# imu.net
KiCad netlist of a schematic drawn in Altium Designer
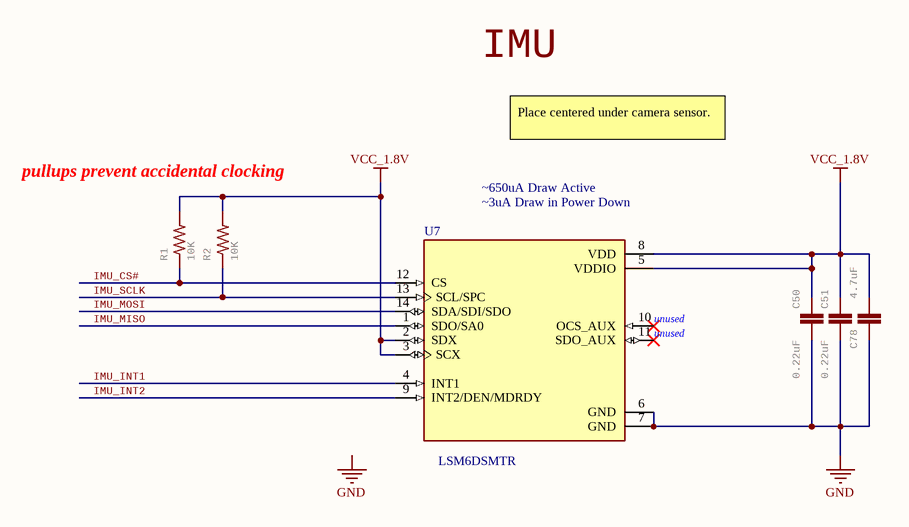
[diagram p0: imu.SchDoc]

(export (version "E")
  (design (tool "Eeschema 10.0.6"))
  (components
    (comp (ref "C50")
      (value "0.22uF")
      (footprint "C0201")
      (description "CAPACITOR, European symbol")
      (fields (field (name "MPN") "GRM033R60J224ME15D"))
      (libsource (lib "openmv-ae3") (part "C-EUC0201"))
    )
    (comp (ref "C51")
      (value "0.22uF")
      (footprint "C0201")
      (description "CAPACITOR, European symbol")
      (fields (field (name "MPN") "GRM033R60J224ME15D"))
      (libsource (lib "openmv-ae3") (part "C-EUC0201"))
    )
    (comp (ref "C78")
      (value "4.7uF")
      (footprint "0402-CAP")
      (description "0402 (1005 Metric) Nick Garner - TeleSense")
      (fields (field (name "MPN") "JMK105BBJ475MV-F"))
      (libsource (lib "openmv-ae3") (part "CAP_0402"))
    )
    (comp (ref "R1")
      (value "10K")
      (footprint "R0201")
      (fields (field (name "LIBRARYNAME") "sfe"))
      (libsource (lib "openmv-ae3") (part "RESISTOR0402-RES"))
    )
    (comp (ref "R2")
      (value "10K")
      (footprint "R0201")
      (fields (field (name "LIBRARYNAME") "sfe"))
      (libsource (lib "openmv-ae3") (part "RESISTOR0402-RES"))
    )
    (comp (ref "U7")
      (value "~")
      (footprint "LSM6DSMTR")
      (description "Accelerometer, Gyroscope, Temperature, 6 Axis Sensor IÂ²C, SPI Output")
      (fields
        (field (name "MF") "STMicroelectronics")
        (field (name "MP") "LSM6DSMTR")
        (field (name "MPN") "LSM6DSMTR")
      )
      (libsource (lib "openmv-ae3") (part "LSM6DSMTR"))
    )
  )
  (nets
    (net (code "1") (name "/IMU_CS#") (class "Default")
      (node (ref "R1") (pin "1") (pinfunction "1_1") (pintype "passive"))
      (node (ref "U7") (pin "12") (pinfunction "CS_12") (pintype "input"))
    )
    (net (code "2") (name "/IMU_INT1") (class "Default")
      (node (ref "U7") (pin "4") (pinfunction "INT1_4") (pintype "input"))
    )
    (net (code "3") (name "/IMU_INT2") (class "Default")
      (node (ref "U7") (pin "9") (pinfunction "INT2/DEN/MDRDY_9") (pintype "input"))
    )
    (net (code "4") (name "/IMU_MISO") (class "Default")
      (node (ref "U7") (pin "1") (pinfunction "SDO/SA0_1") (pintype "bidirectional"))
    )
    (net (code "5") (name "/IMU_MOSI") (class "Default")
      (node (ref "U7") (pin "14") (pinfunction "SDA/SDI/SDO_14") (pintype "bidirectional"))
    )
    (net (code "6") (name "/IMU_SCLK") (class "Default")
      (node (ref "R2") (pin "1") (pinfunction "1_1") (pintype "passive"))
      (node (ref "U7") (pin "13") (pinfunction "SCL/SPC_13") (pintype "input"))
    )
    (net (code "7") (name "GND") (class "Default")
      (node (ref "C50") (pin "2") (pinfunction "2_2") (pintype "passive"))
      (node (ref "C51") (pin "2") (pinfunction "2_2") (pintype "passive"))
      (node (ref "C78") (pin "1") (pinfunction "1_1") (pintype "passive"))
      (node (ref "U7") (pin "6") (pinfunction "GND_6") (pintype "power_in"))
      (node (ref "U7") (pin "7") (pinfunction "GND_7") (pintype "power_in"))
    )
    (net (code "8") (name "VCC_1.8V") (class "Default")
      (node (ref "C50") (pin "1") (pinfunction "1_1") (pintype "passive"))
      (node (ref "C51") (pin "1") (pinfunction "1_1") (pintype "passive"))
      (node (ref "C78") (pin "2") (pinfunction "2_2") (pintype "passive"))
      (node (ref "R1") (pin "2") (pinfunction "2_2") (pintype "passive"))
      (node (ref "R2") (pin "2") (pinfunction "2_2") (pintype "passive"))
      (node (ref "U7") (pin "2") (pinfunction "SDX_2") (pintype "bidirectional"))
      (node (ref "U7") (pin "3") (pinfunction "SCX_3") (pintype "bidirectional"))
      (node (ref "U7") (pin "5") (pinfunction "VDDIO_5") (pintype "power_in"))
      (node (ref "U7") (pin "8") (pinfunction "VDD_8") (pintype "power_in"))
    )
    (net (code "9") (name "unconnected-(U7-OCS_AUX-Pad10)") (class "Default")
      (node (ref "U7") (pin "10") (pinfunction "OCS_AUX_10") (pintype "input+no_connect"))
    )
    (net (code "10") (name "unconnected-(U7-SDO_AUX-Pad11)") (class "Default")
      (node (ref "U7") (pin "11") (pinfunction "SDO_AUX_11") (pintype "bidirectional+no_connect"))
    )
  )
)
